# ARM2.net
KiCad netlist of a schematic drawn in Altium Designer
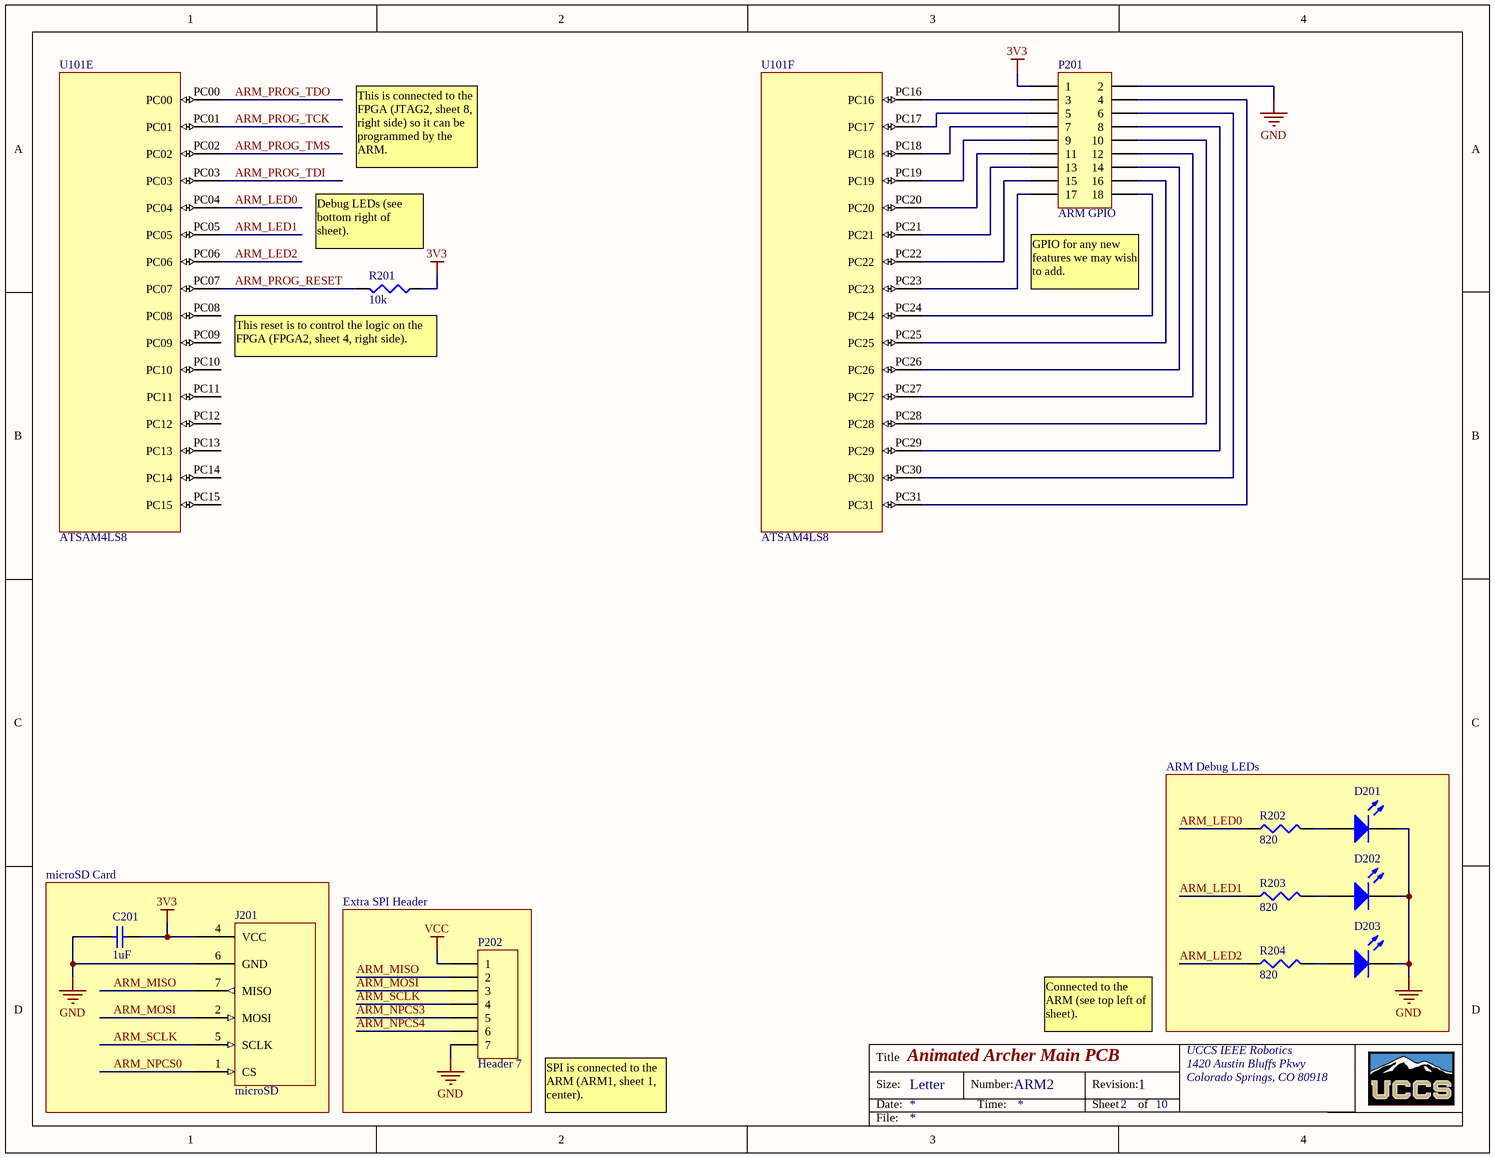
[diagram p0: ARM2.SchDoc]

(export (version "E")
  (design (tool "Eeschema 10.0.6"))
  (components
    (comp (ref "C201")
      (value "1uF")
      (footprint "1608[0603]")
      (description "Capacitor (Semiconductor SIM Model)")
      (fields (field (name "Comment") "0.1uF") (field (name "PUBLISHER") "Altium Limited"))
      (libsource (lib "Miscellaneous Devices") (part "Cap Semi"))
    )
    (comp (ref "D201")
      (value "Green")
      (footprint "1608[0603]")
      (description "Typical RED, GREEN, YELLOW, AMBER GaAs LED")
      (fields (field (name "PUBLISHER") "Altium Limited"))
      (libsource (lib "Miscellaneous Devices") (part "LED2"))
    )
    (comp (ref "D202")
      (value "Green")
      (footprint "1608[0603]")
      (description "Typical RED, GREEN, YELLOW, AMBER GaAs LED")
      (fields (field (name "PUBLISHER") "Altium Limited"))
      (libsource (lib "Miscellaneous Devices") (part "LED2"))
    )
    (comp (ref "D203")
      (value "Green")
      (footprint "1608[0603]")
      (description "Typical RED, GREEN, YELLOW, AMBER GaAs LED")
      (fields (field (name "PUBLISHER") "Altium Limited"))
      (libsource (lib "Miscellaneous Devices") (part "LED2"))
    )
    (comp (ref "J201")
      (value "microSD")
      (footprint "500873-0806")
      (description "microSD Memory Card Connector")
      (libsource (lib "Animated Archer") (part "500873-0806"))
    )
    (comp (ref "P201")
      (value "ARM GPIO")
      (footprint "HDR2X9")
      (description "Header, 9-Pin, Dual row")
      (fields (field (name "PUBLISHER") "Altium Limited"))
      (libsource (lib "Miscellaneous Connectors") (part "Header 9X2"))
    )
    (comp (ref "P202")
      (value "Header 7")
      (footprint "HDR1X7")
      (description "Header, 7-Pin")
      (fields (field (name "PUBLISHER") "Altium Limited"))
      (libsource (lib "Miscellaneous Connectors") (part "Header 7"))
    )
    (comp (ref "R201")
      (value "10k")
      (footprint "J1-0603")
      (description "Resistor")
      (fields (field (name "Comment") "Res3") (field (name "PUBLISHER") "Altium Limited"))
      (libsource (lib "Miscellaneous Devices") (part "Res3"))
    )
    (comp (ref "R202")
      (value "820")
      (footprint "J1-0603")
      (description "Resistor")
      (fields (field (name "Comment") "Res3") (field (name "PUBLISHER") "Altium Limited"))
      (libsource (lib "Miscellaneous Devices") (part "Res3"))
    )
    (comp (ref "R203")
      (value "820")
      (footprint "J1-0603")
      (description "Resistor")
      (fields (field (name "Comment") "Res3") (field (name "PUBLISHER") "Altium Limited"))
      (libsource (lib "Miscellaneous Devices") (part "Res3"))
    )
    (comp (ref "R204")
      (value "820")
      (footprint "J1-0603")
      (description "Resistor")
      (fields (field (name "Comment") "Res3") (field (name "PUBLISHER") "Altium Limited"))
      (libsource (lib "Miscellaneous Devices") (part "Res3"))
    )
    (comp (ref "U101")
      (value "ATSAM4LS8")
      (footprint "LQFP100_N")
      (description "Atmel SAM4L ARM Cortex-M4 MCU (ATSAM4LS8CA-CFU)")
      (libsource (lib "Animated Archer") (part "ATSAM4LS8"))
    )
  )
  (nets
    (net (code "1") (name "/ARM_LED0") (class "Default")
      (node (ref "R202") (pin "1") (pinfunction "1_1") (pintype "passive"))
      (node (ref "U101") (pin "PC04") (pinfunction "PC04_PC04") (pintype "bidirectional"))
    )
    (net (code "2") (name "/ARM_LED1") (class "Default")
      (node (ref "R203") (pin "1") (pinfunction "1_1") (pintype "passive"))
      (node (ref "U101") (pin "PC05") (pinfunction "PC05_PC05") (pintype "bidirectional"))
    )
    (net (code "3") (name "/ARM_LED2") (class "Default")
      (node (ref "R204") (pin "1") (pinfunction "1_1") (pintype "passive"))
      (node (ref "U101") (pin "PC06") (pinfunction "PC06_PC06") (pintype "bidirectional"))
    )
    (net (code "4") (name "/ARM_MISO") (class "Default")
      (node (ref "J201") (pin "7") (pinfunction "MISO_7") (pintype "output"))
      (node (ref "P202") (pin "2") (pinfunction "2_2") (pintype "passive"))
    )
    (net (code "5") (name "/ARM_MOSI") (class "Default")
      (node (ref "J201") (pin "2") (pinfunction "MOSI_2") (pintype "input"))
      (node (ref "P202") (pin "3") (pinfunction "3_3") (pintype "passive"))
    )
    (net (code "6") (name "/ARM_NPCS0") (class "Default")
      (node (ref "J201") (pin "1") (pinfunction "CS_1") (pintype "input"))
    )
    (net (code "7") (name "/ARM_NPCS3") (class "Default")
      (node (ref "P202") (pin "5") (pinfunction "5_5") (pintype "passive"))
    )
    (net (code "8") (name "/ARM_NPCS4") (class "Default")
      (node (ref "P202") (pin "6") (pinfunction "6_6") (pintype "passive"))
    )
    (net (code "9") (name "/ARM_PROG_RESET") (class "Default")
      (node (ref "R201") (pin "2") (pinfunction "2_2") (pintype "passive"))
      (node (ref "U101") (pin "PC07") (pinfunction "PC07_PC07") (pintype "bidirectional"))
    )
    (net (code "10") (name "/ARM_PROG_TCK") (class "Default")
      (node (ref "U101") (pin "PC01") (pinfunction "PC01_PC01") (pintype "bidirectional"))
    )
    (net (code "11") (name "/ARM_PROG_TDI") (class "Default")
      (node (ref "U101") (pin "PC03") (pinfunction "PC03_PC03") (pintype "bidirectional"))
    )
    (net (code "12") (name "/ARM_PROG_TDO") (class "Default")
      (node (ref "U101") (pin "PC00") (pinfunction "PC00_PC00") (pintype "bidirectional"))
    )
    (net (code "13") (name "/ARM_PROG_TMS") (class "Default")
      (node (ref "U101") (pin "PC02") (pinfunction "PC02_PC02") (pintype "bidirectional"))
    )
    (net (code "14") (name "/ARM_SCLK") (class "Default")
      (node (ref "J201") (pin "5") (pinfunction "SCLK_5") (pintype "input"))
      (node (ref "P202") (pin "4") (pinfunction "4_4") (pintype "passive"))
    )
    (net (code "15") (name "3V3") (class "Default")
      (node (ref "C201") (pin "1") (pinfunction "1_1") (pintype "passive"))
      (node (ref "J201") (pin "4") (pinfunction "VCC_4") (pintype "power_in"))
      (node (ref "P201") (pin "1") (pinfunction "1_1") (pintype "passive"))
      (node (ref "R201") (pin "1") (pinfunction "1_1") (pintype "passive"))
    )
    (net (code "16") (name "GND") (class "Default")
      (node (ref "C201") (pin "2") (pinfunction "2_2") (pintype "passive"))
      (node (ref "D201") (pin "2") (pinfunction "K_2") (pintype "passive"))
      (node (ref "D202") (pin "2") (pinfunction "K_2") (pintype "passive"))
      (node (ref "D203") (pin "2") (pinfunction "K_2") (pintype "passive"))
      (node (ref "J201") (pin "6") (pinfunction "GND_6") (pintype "power_in"))
      (node (ref "P201") (pin "2") (pinfunction "2_2") (pintype "passive"))
      (node (ref "P202") (pin "7") (pinfunction "7_7") (pintype "passive"))
    )
    (net (code "17") (name "Net-(D201-A)") (class "Default")
      (node (ref "D201") (pin "1") (pinfunction "A_1") (pintype "passive"))
      (node (ref "R202") (pin "2") (pinfunction "2_2") (pintype "passive"))
    )
    (net (code "18") (name "Net-(D202-A)") (class "Default")
      (node (ref "D202") (pin "1") (pinfunction "A_1") (pintype "passive"))
      (node (ref "R203") (pin "2") (pinfunction "2_2") (pintype "passive"))
    )
    (net (code "19") (name "Net-(D203-A)") (class "Default")
      (node (ref "D203") (pin "1") (pinfunction "A_1") (pintype "passive"))
      (node (ref "R204") (pin "2") (pinfunction "2_2") (pintype "passive"))
    )
    (net (code "20") (name "Net-(P201-Pad3)") (class "Default")
      (node (ref "P201") (pin "3") (pinfunction "3_3") (pintype "passive"))
      (node (ref "U101") (pin "PC16") (pinfunction "PC16_PC16") (pintype "bidirectional"))
    )
    (net (code "21") (name "Net-(P201-Pad4)") (class "Default")
      (node (ref "P201") (pin "4") (pinfunction "4_4") (pintype "passive"))
      (node (ref "U101") (pin "PC31") (pinfunction "PC31_PC31") (pintype "bidirectional"))
    )
    (net (code "22") (name "Net-(P201-Pad5)") (class "Default")
      (node (ref "P201") (pin "5") (pinfunction "5_5") (pintype "passive"))
      (node (ref "U101") (pin "PC17") (pinfunction "PC17_PC17") (pintype "bidirectional"))
    )
    (net (code "23") (name "Net-(P201-Pad6)") (class "Default")
      (node (ref "P201") (pin "6") (pinfunction "6_6") (pintype "passive"))
      (node (ref "U101") (pin "PC30") (pinfunction "PC30_PC30") (pintype "bidirectional"))
    )
    (net (code "24") (name "Net-(P201-Pad7)") (class "Default")
      (node (ref "P201") (pin "7") (pinfunction "7_7") (pintype "passive"))
      (node (ref "U101") (pin "PC18") (pinfunction "PC18_PC18") (pintype "bidirectional"))
    )
    (net (code "25") (name "Net-(P201-Pad8)") (class "Default")
      (node (ref "P201") (pin "8") (pinfunction "8_8") (pintype "passive"))
      (node (ref "U101") (pin "PC29") (pinfunction "PC29_PC29") (pintype "bidirectional"))
    )
    (net (code "26") (name "Net-(P201-Pad9)") (class "Default")
      (node (ref "P201") (pin "9") (pinfunction "9_9") (pintype "passive"))
      (node (ref "U101") (pin "PC19") (pinfunction "PC19_PC19") (pintype "bidirectional"))
    )
    (net (code "27") (name "Net-(P201-Pad10)") (class "Default")
      (node (ref "P201") (pin "10") (pinfunction "10_10") (pintype "passive"))
      (node (ref "U101") (pin "PC28") (pinfunction "PC28_PC28") (pintype "bidirectional"))
    )
    (net (code "28") (name "Net-(P201-Pad11)") (class "Default")
      (node (ref "P201") (pin "11") (pinfunction "11_11") (pintype "passive"))
      (node (ref "U101") (pin "PC20") (pinfunction "PC20_PC20") (pintype "bidirectional"))
    )
    (net (code "29") (name "Net-(P201-Pad12)") (class "Default")
      (node (ref "P201") (pin "12") (pinfunction "12_12") (pintype "passive"))
      (node (ref "U101") (pin "PC27") (pinfunction "PC27_PC27") (pintype "bidirectional"))
    )
    (net (code "30") (name "Net-(P201-Pad13)") (class "Default")
      (node (ref "P201") (pin "13") (pinfunction "13_13") (pintype "passive"))
      (node (ref "U101") (pin "PC21") (pinfunction "PC21_PC21") (pintype "bidirectional"))
    )
    (net (code "31") (name "Net-(P201-Pad14)") (class "Default")
      (node (ref "P201") (pin "14") (pinfunction "14_14") (pintype "passive"))
      (node (ref "U101") (pin "PC26") (pinfunction "PC26_PC26") (pintype "bidirectional"))
    )
    (net (code "32") (name "Net-(P201-Pad15)") (class "Default")
      (node (ref "P201") (pin "15") (pinfunction "15_15") (pintype "passive"))
      (node (ref "U101") (pin "PC22") (pinfunction "PC22_PC22") (pintype "bidirectional"))
    )
    (net (code "33") (name "Net-(P201-Pad16)") (class "Default")
      (node (ref "P201") (pin "16") (pinfunction "16_16") (pintype "passive"))
      (node (ref "U101") (pin "PC25") (pinfunction "PC25_PC25") (pintype "bidirectional"))
    )
    (net (code "34") (name "Net-(P201-Pad17)") (class "Default")
      (node (ref "P201") (pin "17") (pinfunction "17_17") (pintype "passive"))
      (node (ref "U101") (pin "PC23") (pinfunction "PC23_PC23") (pintype "bidirectional"))
    )
    (net (code "35") (name "Net-(P201-Pad18)") (class "Default")
      (node (ref "P201") (pin "18") (pinfunction "18_18") (pintype "passive"))
      (node (ref "U101") (pin "PC24") (pinfunction "PC24_PC24") (pintype "bidirectional"))
    )
    (net (code "36") (name "VCC") (class "Default")
      (node (ref "P202") (pin "1") (pinfunction "1_1") (pintype "passive"))
    )
    (net (code "37") (name "unconnected-(U101-PadPC08)") (class "Default")
      (node (ref "U101") (pin "PC08") (pinfunction "PC08_PC08") (pintype "bidirectional"))
    )
    (net (code "38") (name "unconnected-(U101-PadPC09)") (class "Default")
      (node (ref "U101") (pin "PC09") (pinfunction "PC09_PC09") (pintype "bidirectional"))
    )
    (net (code "39") (name "unconnected-(U101-PadPC10)") (class "Default")
      (node (ref "U101") (pin "PC10") (pinfunction "PC10_PC10") (pintype "bidirectional"))
    )
    (net (code "40") (name "unconnected-(U101-PadPC11)") (class "Default")
      (node (ref "U101") (pin "PC11") (pinfunction "PC11_PC11") (pintype "bidirectional"))
    )
    (net (code "41") (name "unconnected-(U101-PadPC12)") (class "Default")
      (node (ref "U101") (pin "PC12") (pinfunction "PC12_PC12") (pintype "bidirectional"))
    )
    (net (code "42") (name "unconnected-(U101-PadPC13)") (class "Default")
      (node (ref "U101") (pin "PC13") (pinfunction "PC13_PC13") (pintype "bidirectional"))
    )
    (net (code "43") (name "unconnected-(U101-PadPC14)") (class "Default")
      (node (ref "U101") (pin "PC14") (pinfunction "PC14_PC14") (pintype "bidirectional"))
    )
    (net (code "44") (name "unconnected-(U101-PadPC15)") (class "Default")
      (node (ref "U101") (pin "PC15") (pinfunction "PC15_PC15") (pintype "bidirectional"))
    )
  )
)
